# Power_adacus_sch.net
KiCad netlist of a schematic drawn in Altium Designer
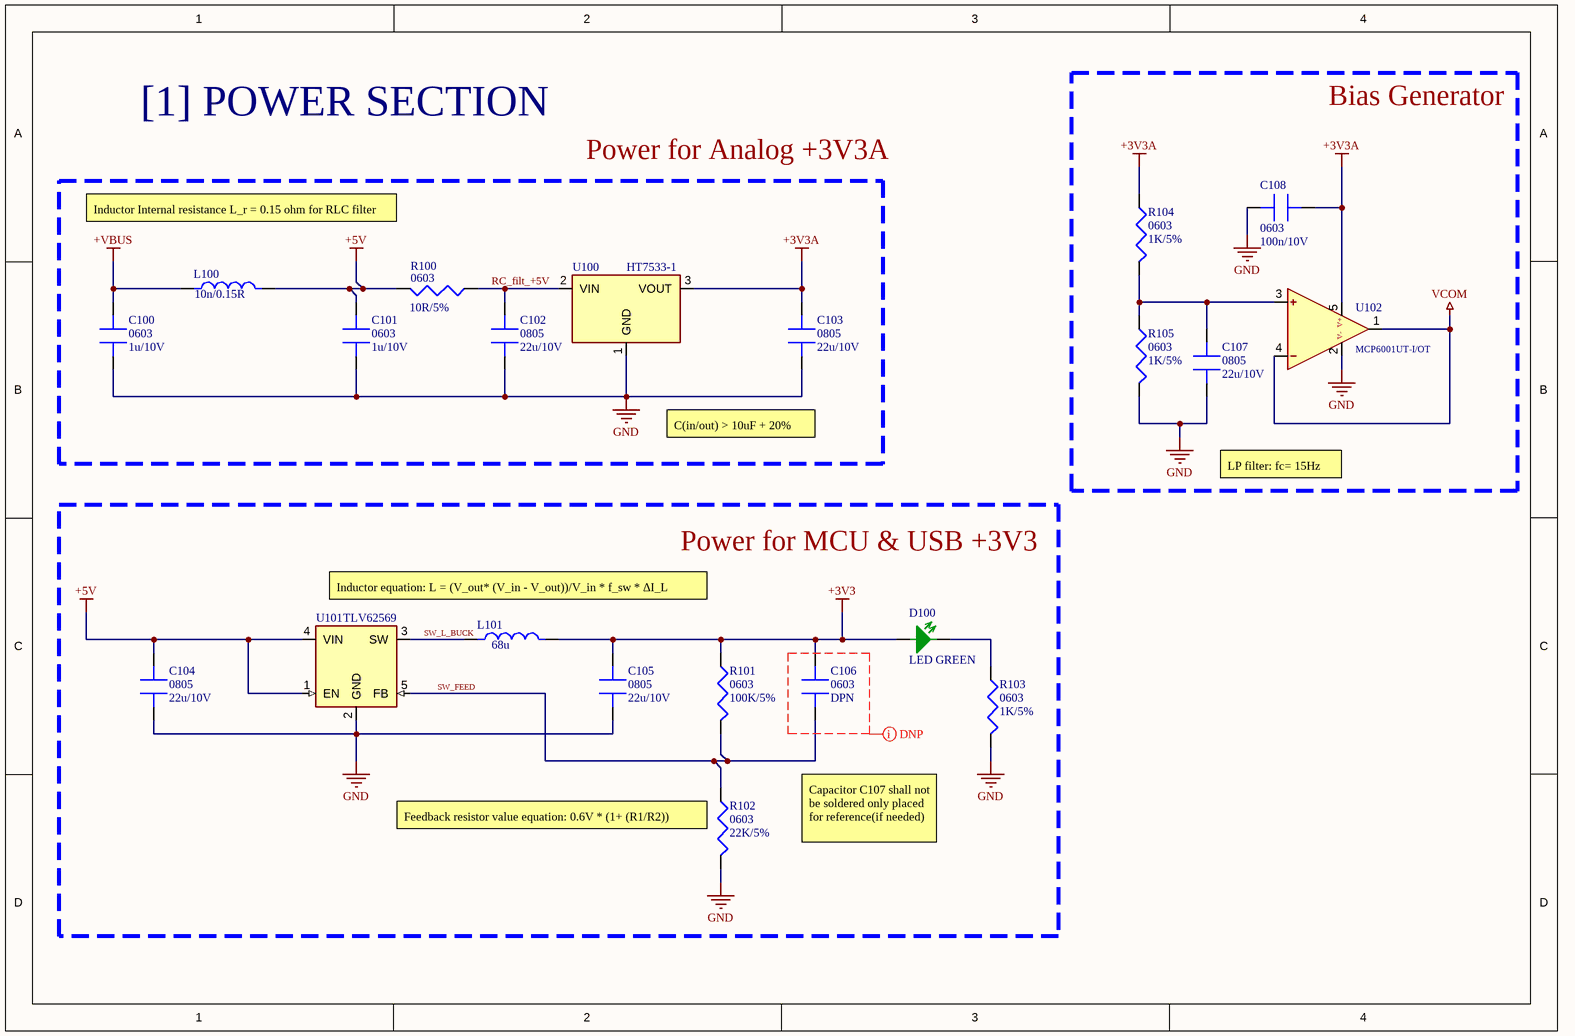
[diagram p0: Power_adacus_sch.SchDoc]

(export (version "E")
  (design (tool "Eeschema 10.0.6"))
  (components
    (comp (ref "C100")
      (value "1u/10V")
      (footprint "[0603] CAPC1608X10M [A-LD]")
      (description "Standard Capacitor")
      (fields (field (name "PACKAGE") "0603") (field (name "Comment") "Capacitor"))
      (libsource (lib "adacus_schlib") (part "Capacitor"))
    )
    (comp (ref "C101")
      (value "1u/10V")
      (footprint "[0603] CAPC1608X10M [A-LD]")
      (description "Standard Capacitor")
      (fields (field (name "PACKAGE") "0603") (field (name "Comment") "Capacitor"))
      (libsource (lib "adacus_schlib") (part "Capacitor"))
    )
    (comp (ref "C102")
      (value "22u/10V")
      (footprint "[0805] CAPC2012X09M [A - LD]")
      (description "Standard Capacitor")
      (fields (field (name "PACKAGE") "0805") (field (name "Comment") "Capacitor"))
      (libsource (lib "adacus_schlib") (part "Capacitor"))
    )
    (comp (ref "C103")
      (value "22u/10V")
      (footprint "[0805] CAPC2012X09M [A - LD]")
      (description "Standard Capacitor")
      (fields (field (name "PACKAGE") "0805") (field (name "Comment") "Capacitor"))
      (libsource (lib "adacus_schlib") (part "Capacitor"))
    )
    (comp (ref "C104")
      (value "22u/10V")
      (footprint "[0805] CAPC2012X09M [A - LD]")
      (description "Standard Capacitor")
      (fields (field (name "PACKAGE") "0805") (field (name "Comment") "Capacitor"))
      (libsource (lib "adacus_schlib") (part "Capacitor"))
    )
    (comp (ref "C105")
      (value "22u/10V")
      (footprint "[0805] CAPC2012X09M [A - LD]")
      (description "Standard Capacitor")
      (fields (field (name "PACKAGE") "0805") (field (name "Comment") "Capacitor"))
      (libsource (lib "adacus_schlib") (part "Capacitor"))
    )
    (comp (ref "C106")
      (value "DPN")
      (footprint "[0603] CAPC1608X10M [A-LD]")
      (description "Standard Capacitor")
      (fields (field (name "PACKAGE") "0603") (field (name "Comment") "Capacitor"))
      (libsource (lib "adacus_schlib") (part "Capacitor"))
    )
    (comp (ref "C107")
      (value "22u/10V")
      (footprint "[0805] CAPC2012X09M [A - LD]")
      (description "Standard Capacitor")
      (fields (field (name "PACKAGE") "0805") (field (name "Comment") "Capacitor"))
      (libsource (lib "adacus_schlib") (part "Capacitor"))
    )
    (comp (ref "C108")
      (value "100n/10V")
      (footprint "[0603] CAPC1608X10M [A-LD]")
      (description "Standard Capacitor")
      (fields (field (name "PACKAGE") "0603") (field (name "Comment") "Capacitor"))
      (libsource (lib "adacus_schlib") (part "Capacitor"))
    )
    (comp (ref "D100")
      (value "LED GREEN")
      (footprint "LEDC2012X120N")
      (description "Standard LED. Green color")
      (libsource (lib "adacus_schlib") (part "LED GREEN"))
    )
    (comp (ref "L100")
      (value "10n/0.15R")
      (footprint "PM0603-10NJ")
      (description "Standard Inductor")
      (fields (field (name "Comment") "Inductor"))
      (libsource (lib "adacus_schlib") (part "Inductor"))
    )
    (comp (ref "L101")
      (value "68u")
      (footprint "[L] SPM10054T-680M-HZR")
      (description "Standard Inductor")
      (fields (field (name "Comment") "Inductor"))
      (libsource (lib "adacus_schlib") (part "Inductor"))
    )
    (comp (ref "R100")
      (value "10R/5%")
      (footprint "[0603] RESC1608X06M [A-LD]")
      (description "Standard Resistor")
      (fields (field (name "PACKAGE") "0603") (field (name "Comment") "Resistor"))
      (libsource (lib "adacus_schlib") (part "Resistor"))
    )
    (comp (ref "R101")
      (value "100K/5%")
      (footprint "[0603] RESC1608X06M [A-LD]")
      (description "Standard Resistor")
      (fields (field (name "PACKAGE") "0603") (field (name "Comment") "Resistor"))
      (libsource (lib "adacus_schlib") (part "Resistor"))
    )
    (comp (ref "R102")
      (value "22K/5%")
      (footprint "[0603] RESC1608X06M [A-LD]")
      (description "Standard Resistor")
      (fields (field (name "PACKAGE") "0603") (field (name "Comment") "Resistor"))
      (libsource (lib "adacus_schlib") (part "Resistor"))
    )
    (comp (ref "R103")
      (value "1K/5%")
      (footprint "[0603] RESC1608X06M [A-LD]")
      (description "Standard Resistor")
      (fields (field (name "PACKAGE") "0603") (field (name "Comment") "Resistor"))
      (libsource (lib "adacus_schlib") (part "Resistor"))
    )
    (comp (ref "R104")
      (value "1K/5%")
      (footprint "[0603] RESC1608X06M [A-LD]")
      (description "Standard Resistor")
      (fields (field (name "PACKAGE") "0603") (field (name "Comment") "Resistor"))
      (libsource (lib "adacus_schlib") (part "Resistor"))
    )
    (comp (ref "R105")
      (value "1K/5%")
      (footprint "[0603] RESC1608X06M [A-LD]")
      (description "Standard Resistor")
      (fields (field (name "PACKAGE") "0603") (field (name "Comment") "Resistor"))
      (libsource (lib "adacus_schlib") (part "Resistor"))
    )
    (comp (ref "U100")
      (value "HT7533-1")
      (footprint "SOT89-150P354X160-3M")
      (description "100mA TinyPower LDO")
      (libsource (lib "adacus_schlib") (part "HT7533-1"))
    )
    (comp (ref "U101")
      (value "TLV62569")
      (footprint "SOT95P280X145-5M")
      (description "2-A High Efficiency Synchronous Buck Converter in SOT Package")
      (libsource (lib "adacus_schlib") (part "TLV62569"))
    )
    (comp (ref "U102")
      (value "MCP6001UT-I/OT")
      (footprint "SOT95P270X145-5M")
      (description "Operational Amplifiers - Op Amps Single 1.8V 1MHz")
      (libsource (lib "adacus_schlib") (part "MCP6001UT-I/OT"))
    )
  )
  (nets
    (net (code "1") (name "+3V3") (class "Default")
      (node (ref "C105") (pin "2") (pinfunction "2_2") (pintype "passive"))
      (node (ref "C106") (pin "2") (pinfunction "2_2") (pintype "passive"))
      (node (ref "D100") (pin "1") (pinfunction "1_1") (pintype "passive"))
      (node (ref "L101") (pin "1") (pinfunction "1_1") (pintype "passive"))
      (node (ref "R101") (pin "2") (pinfunction "2_2") (pintype "passive"))
    )
    (net (code "2") (name "+3V3A") (class "Default")
      (node (ref "C103") (pin "2") (pinfunction "2_2") (pintype "passive"))
      (node (ref "C108") (pin "1") (pinfunction "1_1") (pintype "passive"))
      (node (ref "R104") (pin "2") (pinfunction "2_2") (pintype "passive"))
      (node (ref "U100") (pin "3") (pinfunction "VOUT_3") (pintype "power_in"))
      (node (ref "U102") (pin "5") (pinfunction "VDD_5") (pintype "passive"))
    )
    (net (code "3") (name "+5V") (class "Default")
      (node (ref "C101") (pin "2") (pinfunction "2_2") (pintype "passive"))
      (node (ref "C104") (pin "2") (pinfunction "2_2") (pintype "passive"))
      (node (ref "L100") (pin "1") (pinfunction "1_1") (pintype "passive"))
      (node (ref "R100") (pin "1") (pinfunction "1_1") (pintype "passive"))
      (node (ref "U101") (pin "1") (pinfunction "EN_1") (pintype "input"))
      (node (ref "U101") (pin "4") (pinfunction "VIN_4") (pintype "power_in"))
    )
    (net (code "4") (name "+VBUS") (class "Default")
      (node (ref "C100") (pin "2") (pinfunction "2_2") (pintype "passive"))
      (node (ref "L100") (pin "2") (pinfunction "2_2") (pintype "passive"))
    )
    (net (code "5") (name "/RC_filt_+5V") (class "Default")
      (node (ref "C102") (pin "2") (pinfunction "2_2") (pintype "passive"))
      (node (ref "R100") (pin "2") (pinfunction "2_2") (pintype "passive"))
      (node (ref "U100") (pin "2") (pinfunction "VIN_2") (pintype "power_in"))
    )
    (net (code "6") (name "/SW_FEED") (class "Default")
      (node (ref "C106") (pin "1") (pinfunction "1_1") (pintype "passive"))
      (node (ref "R101") (pin "1") (pinfunction "1_1") (pintype "passive"))
      (node (ref "R102") (pin "2") (pinfunction "2_2") (pintype "passive"))
      (node (ref "U101") (pin "5") (pinfunction "FB_5") (pintype "input"))
    )
    (net (code "7") (name "/SW_L_BUCK") (class "Default")
      (node (ref "L101") (pin "2") (pinfunction "2_2") (pintype "passive"))
      (node (ref "U101") (pin "3") (pinfunction "SW_3") (pintype "power_in"))
    )
    (net (code "8") (name "GND") (class "Default")
      (node (ref "C100") (pin "1") (pinfunction "1_1") (pintype "passive"))
      (node (ref "C101") (pin "1") (pinfunction "1_1") (pintype "passive"))
      (node (ref "C102") (pin "1") (pinfunction "1_1") (pintype "passive"))
      (node (ref "C103") (pin "1") (pinfunction "1_1") (pintype "passive"))
      (node (ref "C104") (pin "1") (pinfunction "1_1") (pintype "passive"))
      (node (ref "C105") (pin "1") (pinfunction "1_1") (pintype "passive"))
      (node (ref "C107") (pin "1") (pinfunction "1_1") (pintype "passive"))
      (node (ref "C108") (pin "2") (pinfunction "2_2") (pintype "passive"))
      (node (ref "R102") (pin "1") (pinfunction "1_1") (pintype "passive"))
      (node (ref "R103") (pin "1") (pinfunction "1_1") (pintype "passive"))
      (node (ref "R105") (pin "1") (pinfunction "1_1") (pintype "passive"))
      (node (ref "U100") (pin "1") (pinfunction "GND_1") (pintype "passive"))
      (node (ref "U101") (pin "2") (pinfunction "GND_2") (pintype "power_in"))
      (node (ref "U102") (pin "2") (pinfunction "VSS_2") (pintype "passive"))
    )
    (net (code "9") (name "Net-(D100-Pad2)") (class "Default")
      (node (ref "D100") (pin "2") (pinfunction "2_2") (pintype "passive"))
      (node (ref "R103") (pin "2") (pinfunction "2_2") (pintype "passive"))
    )
    (net (code "10") (name "Net-(U102-+)") (class "Default")
      (node (ref "C107") (pin "2") (pinfunction "2_2") (pintype "passive"))
      (node (ref "R104") (pin "1") (pinfunction "1_1") (pintype "passive"))
      (node (ref "R105") (pin "2") (pinfunction "2_2") (pintype "passive"))
      (node (ref "U102") (pin "3") (pinfunction "+_3") (pintype "passive"))
    )
    (net (code "11") (name "VCOM") (class "Default")
      (node (ref "U102") (pin "1") (pinfunction "OUT_1") (pintype "passive"))
      (node (ref "U102") (pin "4") (pinfunction "-_4") (pintype "passive"))
    )
  )
)
